# 004_FOC_RS_Interface.net
KiCad netlist of a schematic drawn in Altium Designer
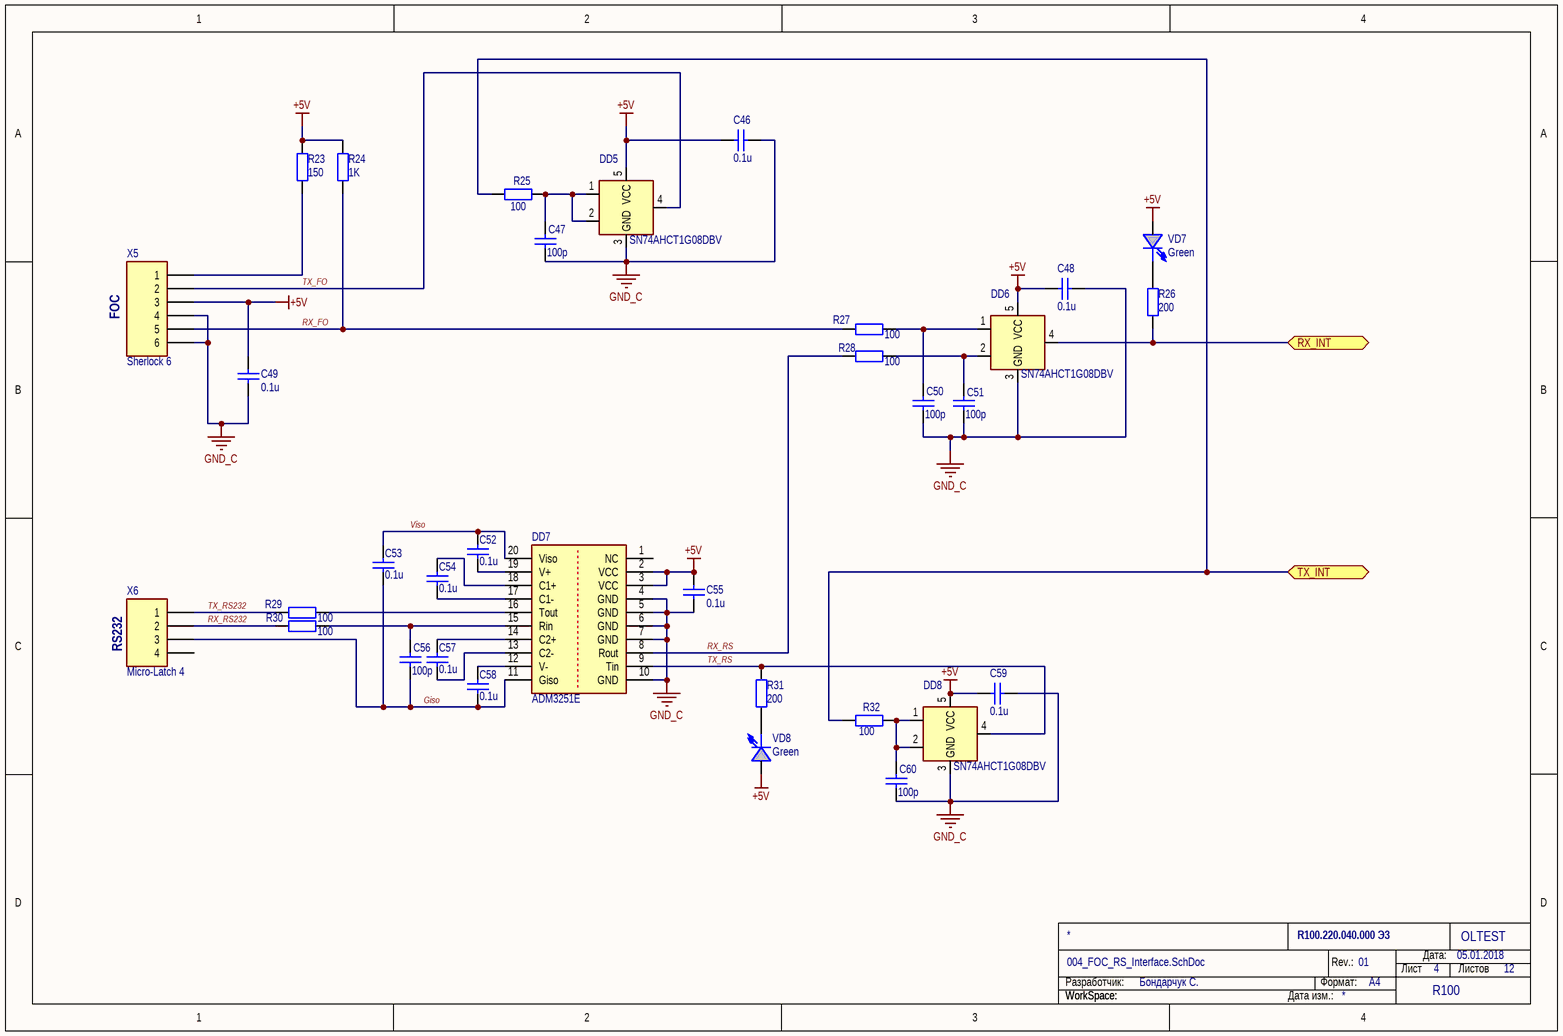
[diagram p0: 004_FOC_RS_Interface.SchDoc]

(export (version "E")
  (design (tool "Eeschema 10.0.6"))
  (components
    (comp (ref "C46")
      (value "0.1u")
      (footprint "mainLib:SMD_C_0603")
      (description "SMD C 0603 MURATA 50V 10% X7R")
      (fields (field (name "PARTNUMBER") "GRM188R71H104K") (field (name "MANUFACTURER") "MURATA"))
      (libsource (lib "mainRCLib") (part "C0603 0.1u 50V 10%"))
    )
    (comp (ref "C47")
      (value "100p")
      (footprint "mainLib:SMD_C_0603")
      (description "SMD C 0603 MURATA 100V 5% NP0")
      (fields (field (name "PARTNUMBER") "GRM1885C2A101JA01") (field (name "MANUFACTURER") "MURATA"))
      (libsource (lib "mainRCLib") (part "C0603 100p 100V 5%"))
    )
    (comp (ref "C48")
      (value "0.1u")
      (footprint "mainLib:SMD_C_0603")
      (description "SMD C 0603 MURATA 50V 10% X7R")
      (fields (field (name "PARTNUMBER") "GRM188R71H104K") (field (name "MANUFACTURER") "MURATA"))
      (libsource (lib "mainRCLib") (part "C0603 0.1u 50V 10%"))
    )
    (comp (ref "C49")
      (value "0.1u")
      (footprint "mainLib:SMD_C_0603")
      (description "SMD C 0603 MURATA 50V 10% X7R")
      (fields (field (name "PARTNUMBER") "GRM188R71H104K") (field (name "MANUFACTURER") "MURATA"))
      (libsource (lib "mainRCLib") (part "C0603 0.1u 50V 10%"))
    )
    (comp (ref "C50")
      (value "100p")
      (footprint "mainLib:SMD_C_0603")
      (description "SMD C 0603 MURATA 100V 5% NP0")
      (fields (field (name "PARTNUMBER") "GRM1885C2A101JA01") (field (name "MANUFACTURER") "MURATA"))
      (libsource (lib "mainRCLib") (part "C0603 100p 100V 5%"))
    )
    (comp (ref "C51")
      (value "100p")
      (footprint "mainLib:SMD_C_0603")
      (description "SMD C 0603 MURATA 100V 5% NP0")
      (fields (field (name "PARTNUMBER") "GRM1885C2A101JA01") (field (name "MANUFACTURER") "MURATA"))
      (libsource (lib "mainRCLib") (part "C0603 100p 100V 5%"))
    )
    (comp (ref "C52")
      (value "0.1u")
      (footprint "mainLib:SMD_C_0603")
      (description "SMD C 0603 MURATA 50V 10% X7R")
      (fields (field (name "PARTNUMBER") "GRM188R71H104K") (field (name "MANUFACTURER") "MURATA"))
      (libsource (lib "mainRCLib") (part "C0603 0.1u 50V 10%"))
    )
    (comp (ref "C53")
      (value "0.1u")
      (footprint "mainLib:SMD_C_0603")
      (description "SMD C 0603 MURATA 50V 10% X7R")
      (fields (field (name "PARTNUMBER") "GRM188R71H104K") (field (name "MANUFACTURER") "MURATA"))
      (libsource (lib "mainRCLib") (part "C0603 0.1u 50V 10%"))
    )
    (comp (ref "C54")
      (value "0.1u")
      (footprint "mainLib:SMD_C_0603")
      (description "SMD C 0603 MURATA 50V 10% X7R")
      (fields (field (name "PARTNUMBER") "GRM188R71H104K") (field (name "MANUFACTURER") "MURATA"))
      (libsource (lib "mainRCLib") (part "C0603 0.1u 50V 10%"))
    )
    (comp (ref "C55")
      (value "0.1u")
      (footprint "mainLib:SMD_C_0603")
      (description "SMD C 0603 MURATA 50V 10% X7R")
      (fields (field (name "PARTNUMBER") "GRM188R71H104K") (field (name "MANUFACTURER") "MURATA"))
      (libsource (lib "mainRCLib") (part "C0603 0.1u 50V 10%"))
    )
    (comp (ref "C56")
      (value "100p")
      (footprint "mainLib:SMD_C_0603")
      (description "SMD C 0603 MURATA 100V 5% NP0")
      (fields (field (name "PARTNUMBER") "GRM1885C2A101JA01") (field (name "MANUFACTURER") "MURATA"))
      (libsource (lib "mainRCLib") (part "C0603 100p 100V 5%"))
    )
    (comp (ref "C57")
      (value "0.1u")
      (footprint "mainLib:SMD_C_0603")
      (description "SMD C 0603 MURATA 50V 10% X7R")
      (fields (field (name "PARTNUMBER") "GRM188R71H104K") (field (name "MANUFACTURER") "MURATA"))
      (libsource (lib "mainRCLib") (part "C0603 0.1u 50V 10%"))
    )
    (comp (ref "C58")
      (value "0.1u")
      (footprint "mainLib:SMD_C_0603")
      (description "SMD C 0603 MURATA 50V 10% X7R")
      (fields (field (name "PARTNUMBER") "GRM188R71H104K") (field (name "MANUFACTURER") "MURATA"))
      (libsource (lib "mainRCLib") (part "C0603 0.1u 50V 10%"))
    )
    (comp (ref "C59")
      (value "0.1u")
      (footprint "mainLib:SMD_C_0603")
      (description "SMD C 0603 MURATA 50V 10% X7R")
      (fields (field (name "PARTNUMBER") "GRM188R71H104K") (field (name "MANUFACTURER") "MURATA"))
      (libsource (lib "mainRCLib") (part "C0603 0.1u 50V 10%"))
    )
    (comp (ref "C60")
      (value "100p")
      (footprint "mainLib:SMD_C_0603")
      (description "SMD C 0603 MURATA 100V 5% NP0")
      (fields (field (name "PARTNUMBER") "GRM1885C2A101JA01") (field (name "MANUFACTURER") "MURATA"))
      (libsource (lib "mainRCLib") (part "C0603 100p 100V 5%"))
    )
    (comp (ref "DD5")
      (value "SN74AHCT1G08DBV")
      (footprint "mainLib:SOT-23(DBV)")
      (description "2-in AND")
      (fields (field (name "MANUFACTURER") "Texas Instruments"))
      (libsource (lib "mainLib") (part "SN74AHCT1G08DBV"))
    )
    (comp (ref "DD6")
      (value "SN74AHCT1G08DBV")
      (footprint "mainLib:SOT-23(DBV)")
      (description "2-in AND")
      (fields (field (name "MANUFACTURER") "Texas Instruments"))
      (libsource (lib "mainLib") (part "SN74AHCT1G08DBV"))
    )
    (comp (ref "DD7")
      (value "ADM3251E")
      (footprint "mainLib:RW-20")
      (description "Isolated, Single-Channel, RS-232 Line Driver/Receiver")
      (fields (field (name "MANUFACTURER") "Analog Device") (field (name "PARTNUMBER") "ADM3251EARWZ"))
      (libsource (lib "mainLib") (part "ADM3251E"))
    )
    (comp (ref "DD8")
      (value "SN74AHCT1G08DBV")
      (footprint "mainLib:SOT-23(DBV)")
      (description "2-in AND")
      (fields (field (name "MANUFACTURER") "Texas Instruments"))
      (libsource (lib "mainLib") (part "SN74AHCT1G08DBV"))
    )
    (comp (ref "R23")
      (value "150")
      (footprint "mainLib:SMD_R_0805")
      (description "SMD 0805 VISHAY 0.125W 150V 1% 100ppm")
      (fields (field (name "PARTNUMBER") "CRCW0805150RFK") (field (name "MANUFACTURER") "VISHAY"))
      (libsource (lib "mainRCLib") (part "R0805 150 1%"))
    )
    (comp (ref "R24")
      (value "1K")
      (footprint "mainLib:SMD_R_0603")
      (description "SMD R 0603 VISHAY 0.1W 75V 1% 100ppm")
      (fields (field (name "PARTNUMBER") "CRCW06031K00FK") (field (name "MANUFACTURER") "VISHAY"))
      (libsource (lib "mainRCLib") (part "R0603 1K 1%"))
    )
    (comp (ref "R25")
      (value "100")
      (footprint "SMD_R_0603")
      (description "SMD R 0603 VISHAY 0.1W 75V 1% 100ppm")
      (fields (field (name "PARTNUMBER") "CRCW0603100RFK") (field (name "MANUFACTURER") "VISHAY"))
      (libsource (lib "mainRCLib") (part "R0603 100 1%"))
    )
    (comp (ref "R26")
      (value "200")
      (footprint "mainLib:SMD_R_0805")
      (description "SMD R 0805 VISHAY 0.125W 150V 1% 100ppm")
      (fields (field (name "PARTNUMBER") "CRCW0805200RFK") (field (name "MANUFACTURER") "VISHAY"))
      (libsource (lib "mainRCLib") (part "R0805 200 1%"))
    )
    (comp (ref "R27")
      (value "100")
      (footprint "SMD_R_0603")
      (description "SMD R 0603 VISHAY 0.1W 75V 1% 100ppm")
      (fields (field (name "PARTNUMBER") "CRCW0603100RFK") (field (name "MANUFACTURER") "VISHAY"))
      (libsource (lib "mainRCLib") (part "R0603 100 1%"))
    )
    (comp (ref "R28")
      (value "100")
      (footprint "SMD_R_0603")
      (description "SMD R 0603 VISHAY 0.1W 75V 1% 100ppm")
      (fields (field (name "PARTNUMBER") "CRCW0603100RFK") (field (name "MANUFACTURER") "VISHAY"))
      (libsource (lib "mainRCLib") (part "R0603 100 1%"))
    )
    (comp (ref "R29")
      (value "100")
      (footprint "SMD_R_0603")
      (description "SMD R 0603 VISHAY 0.1W 75V 1% 100ppm")
      (fields (field (name "PARTNUMBER") "CRCW0603100RFK") (field (name "MANUFACTURER") "VISHAY"))
      (libsource (lib "mainRCLib") (part "R0603 100 1%"))
    )
    (comp (ref "R30")
      (value "100")
      (footprint "SMD_R_0603")
      (description "SMD R 0603 VISHAY 0.1W 75V 1% 100ppm")
      (fields (field (name "PARTNUMBER") "CRCW0603100RFK") (field (name "MANUFACTURER") "VISHAY"))
      (libsource (lib "mainRCLib") (part "R0603 100 1%"))
    )
    (comp (ref "R31")
      (value "200")
      (footprint "mainLib:SMD_R_0805")
      (description "SMD R 0805 VISHAY 0.125W 150V 1% 100ppm")
      (fields (field (name "PARTNUMBER") "CRCW0805200RFK") (field (name "MANUFACTURER") "VISHAY"))
      (libsource (lib "mainRCLib") (part "R0805 200 1%"))
    )
    (comp (ref "R32")
      (value "100")
      (footprint "SMD_R_0603")
      (description "SMD R 0603 VISHAY 0.1W 75V 1% 100ppm")
      (fields (field (name "PARTNUMBER") "CRCW0603100RFK") (field (name "MANUFACTURER") "VISHAY"))
      (libsource (lib "mainRCLib") (part "R0603 100 1%"))
    )
    (comp (ref "VD7")
      (value "Green")
      (footprint "mainLib:SMD_LED_LL_Green")
      (description "LED Green SMD")
      (fields (field (name "PARTNUMBER") "LL-S172GC-2A") (field (name "MANUFACTURER") "Lucky Light"))
      (libsource (lib "mainLib") (part "LL-S172GC-2A"))
    )
    (comp (ref "VD8")
      (value "Green")
      (footprint "mainLib:SMD_LED_LL_Green")
      (description "LED Green SMD")
      (fields (field (name "PARTNUMBER") "LL-S172GC-2A") (field (name "MANUFACTURER") "Lucky Light"))
      (libsource (lib "mainLib") (part "LL-S172GC-2A"))
    )
    (comp (ref "X5")
      (value "Sherlock 6")
      (footprint "mainLib:35362-0650")
      (description "Sherlock 6 Side, 2A 125V 2mm")
      (fields (field (name "PARTNUMBER") "35362-0650") (field (name "MANUFACTURER") "MOLEX"))
      (libsource (lib "mainLib") (part "35363-0650"))
    )
    (comp (ref "X6")
      (value "Micro-Latch 4")
      (footprint "mainLib:53253-0470")
      (description "Micro-Latch 4  LS=2 2A 125V PCB")
      (fields (field (name "PARTNUMBER") "53253-0470") (field (name "MANUFACTURER") "MOLEX"))
      (libsource (lib "mainLib") (part "53253-0470"))
    )
  )
  (nets
    (net (code "1") (name "+5V") (class "Default")
      (node (ref "C46") (pin "1") (pinfunction "1_1") (pintype "passive"))
      (node (ref "C48") (pin "1") (pinfunction "1_1") (pintype "passive"))
      (node (ref "C49") (pin "2") (pinfunction "2_2") (pintype "passive"))
      (node (ref "C55") (pin "2") (pinfunction "2_2") (pintype "passive"))
      (node (ref "C59") (pin "1") (pinfunction "1_1") (pintype "passive"))
      (node (ref "DD5") (pin "5") (pinfunction "VCC_5") (pintype "passive"))
      (node (ref "DD6") (pin "5") (pinfunction "VCC_5") (pintype "passive"))
      (node (ref "DD7") (pin "2") (pinfunction "VCC_2") (pintype "power_in"))
      (node (ref "DD7") (pin "3") (pinfunction "VCC_3") (pintype "power_in"))
      (node (ref "DD8") (pin "5") (pinfunction "VCC_5") (pintype "passive"))
      (node (ref "R23") (pin "2") (pinfunction "2_2") (pintype "passive"))
      (node (ref "R24") (pin "2") (pinfunction "2_2") (pintype "passive"))
      (node (ref "VD7") (pin "1") (pinfunction "ANODE_1") (pintype "passive"))
      (node (ref "VD8") (pin "1") (pinfunction "ANODE_1") (pintype "passive"))
      (node (ref "X5") (pin "3") (pinfunction "3_3") (pintype "passive"))
    )
    (net (code "2") (name "/Giso") (class "Default")
      (node (ref "C53") (pin "1") (pinfunction "1_1") (pintype "passive"))
      (node (ref "C56") (pin "1") (pinfunction "1_1") (pintype "passive"))
      (node (ref "C58") (pin "1") (pinfunction "1_1") (pintype "passive"))
      (node (ref "DD7") (pin "11") (pinfunction "Giso_11") (pintype "passive"))
      (node (ref "X6") (pin "3") (pinfunction "3_3") (pintype "passive"))
    )
    (net (code "3") (name "/RX_FO") (class "Default")
      (node (ref "R24") (pin "1") (pinfunction "1_1") (pintype "passive"))
      (node (ref "R27") (pin "1") (pinfunction "1_1") (pintype "passive"))
      (node (ref "X5") (pin "5") (pinfunction "5_5") (pintype "passive"))
    )
    (net (code "4") (name "/RX_INT") (class "Default")
      (node (ref "DD6") (pin "4") (pintype "passive"))
      (node (ref "R26") (pin "1") (pinfunction "1_1") (pintype "passive"))
    )
    (net (code "5") (name "/RX_RS") (class "Default")
      (node (ref "DD7") (pin "8") (pinfunction "Rout_8") (pintype "passive"))
      (node (ref "R28") (pin "1") (pinfunction "1_1") (pintype "passive"))
    )
    (net (code "6") (name "/RX_RS232") (class "Default")
      (node (ref "R30") (pin "1") (pinfunction "1_1") (pintype "passive"))
      (node (ref "X6") (pin "2") (pinfunction "2_2") (pintype "passive"))
    )
    (net (code "7") (name "/TX_FO") (class "Default")
      (node (ref "DD5") (pin "4") (pintype "passive"))
      (node (ref "X5") (pin "2") (pinfunction "2_2") (pintype "passive"))
    )
    (net (code "8") (name "/TX_INT") (class "Default")
      (node (ref "R25") (pin "1") (pinfunction "1_1") (pintype "passive"))
      (node (ref "R32") (pin "1") (pinfunction "1_1") (pintype "passive"))
    )
    (net (code "9") (name "/TX_RS") (class "Default")
      (node (ref "DD7") (pin "9") (pinfunction "Tin_9") (pintype "passive"))
      (node (ref "DD8") (pin "4") (pintype "passive"))
      (node (ref "R31") (pin "2") (pinfunction "2_2") (pintype "passive"))
    )
    (net (code "10") (name "/TX_RS232") (class "Default")
      (node (ref "R29") (pin "1") (pinfunction "1_1") (pintype "passive"))
      (node (ref "X6") (pin "1") (pinfunction "1_1") (pintype "passive"))
    )
    (net (code "11") (name "/Viso") (class "Default")
      (node (ref "C52") (pin "2") (pinfunction "2_2") (pintype "passive"))
      (node (ref "C53") (pin "2") (pinfunction "2_2") (pintype "passive"))
      (node (ref "DD7") (pin "20") (pinfunction "Viso_20") (pintype "passive"))
    )
    (net (code "12") (name "GND_C") (class "Default")
      (node (ref "C46") (pin "2") (pinfunction "2_2") (pintype "passive"))
      (node (ref "C47") (pin "1") (pinfunction "1_1") (pintype "passive"))
      (node (ref "C48") (pin "2") (pinfunction "2_2") (pintype "passive"))
      (node (ref "C49") (pin "1") (pinfunction "1_1") (pintype "passive"))
      (node (ref "C50") (pin "1") (pinfunction "1_1") (pintype "passive"))
      (node (ref "C51") (pin "2") (pinfunction "2_2") (pintype "passive"))
      (node (ref "C55") (pin "1") (pinfunction "1_1") (pintype "passive"))
      (node (ref "C59") (pin "2") (pinfunction "2_2") (pintype "passive"))
      (node (ref "C60") (pin "1") (pinfunction "1_1") (pintype "passive"))
      (node (ref "DD5") (pin "3") (pinfunction "GND_3") (pintype "passive"))
      (node (ref "DD6") (pin "3") (pinfunction "GND_3") (pintype "passive"))
      (node (ref "DD7") (pin "10") (pinfunction "GND_10") (pintype "power_in"))
      (node (ref "DD7") (pin "4") (pinfunction "GND_4") (pintype "power_in"))
      (node (ref "DD7") (pin "5") (pinfunction "GND_5") (pintype "power_in"))
      (node (ref "DD7") (pin "6") (pinfunction "GND_6") (pintype "power_in"))
      (node (ref "DD7") (pin "7") (pinfunction "GND_7") (pintype "power_in"))
      (node (ref "DD8") (pin "3") (pinfunction "GND_3") (pintype "passive"))
      (node (ref "X5") (pin "4") (pinfunction "4_4") (pintype "passive"))
      (node (ref "X5") (pin "6") (pinfunction "6_6") (pintype "passive"))
    )
    (net (code "13") (name "Net-(C47-Pad2)") (class "Default")
      (node (ref "C47") (pin "2") (pinfunction "2_2") (pintype "passive"))
      (node (ref "DD5") (pin "1") (pintype "passive"))
      (node (ref "DD5") (pin "2") (pintype "passive"))
      (node (ref "R25") (pin "2") (pinfunction "2_2") (pintype "passive"))
    )
    (net (code "14") (name "Net-(C50-Pad2)") (class "Default")
      (node (ref "C50") (pin "2") (pinfunction "2_2") (pintype "passive"))
      (node (ref "DD6") (pin "1") (pintype "passive"))
      (node (ref "R27") (pin "2") (pinfunction "2_2") (pintype "passive"))
    )
    (net (code "15") (name "Net-(C51-Pad1)") (class "Default")
      (node (ref "C51") (pin "1") (pinfunction "1_1") (pintype "passive"))
      (node (ref "DD6") (pin "2") (pintype "passive"))
      (node (ref "R28") (pin "2") (pinfunction "2_2") (pintype "passive"))
    )
    (net (code "16") (name "Net-(C60-Pad2)") (class "Default")
      (node (ref "C60") (pin "2") (pinfunction "2_2") (pintype "passive"))
      (node (ref "DD8") (pin "1") (pintype "passive"))
      (node (ref "DD8") (pin "2") (pintype "passive"))
      (node (ref "R32") (pin "2") (pinfunction "2_2") (pintype "passive"))
    )
    (net (code "17") (name "Net-(DD7-C1+)") (class "Default")
      (node (ref "C54") (pin "2") (pinfunction "2_2") (pintype "passive"))
      (node (ref "DD7") (pin "18") (pinfunction "C1+_18") (pintype "passive"))
    )
    (net (code "18") (name "Net-(DD7-C1-)") (class "Default")
      (node (ref "C54") (pin "1") (pinfunction "1_1") (pintype "passive"))
      (node (ref "DD7") (pin "17") (pinfunction "C1-_17") (pintype "passive"))
    )
    (net (code "19") (name "Net-(DD7-C2+)") (class "Default")
      (node (ref "C57") (pin "2") (pinfunction "2_2") (pintype "passive"))
      (node (ref "DD7") (pin "14") (pinfunction "C2+_14") (pintype "passive"))
    )
    (net (code "20") (name "Net-(DD7-C2-)") (class "Default")
      (node (ref "C57") (pin "1") (pinfunction "1_1") (pintype "passive"))
      (node (ref "DD7") (pin "13") (pinfunction "C2-_13") (pintype "passive"))
    )
    (net (code "21") (name "Net-(DD7-Rin)") (class "Default")
      (node (ref "C56") (pin "2") (pinfunction "2_2") (pintype "passive"))
      (node (ref "DD7") (pin "15") (pinfunction "Rin_15") (pintype "passive"))
      (node (ref "R30") (pin "2") (pinfunction "2_2") (pintype "passive"))
    )
    (net (code "22") (name "Net-(DD7-Tout)") (class "Default")
      (node (ref "DD7") (pin "16") (pinfunction "Tout_16") (pintype "passive"))
      (node (ref "R29") (pin "2") (pinfunction "2_2") (pintype "passive"))
    )
    (net (code "23") (name "Net-(DD7-V+)") (class "Default")
      (node (ref "C52") (pin "1") (pinfunction "1_1") (pintype "passive"))
      (node (ref "DD7") (pin "19") (pinfunction "V+_19") (pintype "passive"))
    )
    (net (code "24") (name "Net-(DD7-V-)") (class "Default")
      (node (ref "C58") (pin "2") (pinfunction "2_2") (pintype "passive"))
      (node (ref "DD7") (pin "12") (pinfunction "V-_12") (pintype "passive"))
    )
    (net (code "25") (name "Net-(R23-Pad1)") (class "Default")
      (node (ref "R23") (pin "1") (pinfunction "1_1") (pintype "passive"))
      (node (ref "X5") (pin "1") (pinfunction "1_1") (pintype "passive"))
    )
    (net (code "26") (name "Net-(VD7-CATHODE)") (class "Default")
      (node (ref "R26") (pin "2") (pinfunction "2_2") (pintype "passive"))
      (node (ref "VD7") (pin "2") (pinfunction "CATHODE_2") (pintype "passive"))
    )
    (net (code "27") (name "Net-(VD8-CATHODE)") (class "Default")
      (node (ref "R31") (pin "1") (pinfunction "1_1") (pintype "passive"))
      (node (ref "VD8") (pin "2") (pinfunction "CATHODE_2") (pintype "passive"))
    )
    (net (code "28") (name "unconnected-(DD7-NC-Pad1)") (class "Default")
      (node (ref "DD7") (pin "1") (pinfunction "NC_1") (pintype "passive"))
    )
    (net (code "29") (name "unconnected-(X6-Pad4)") (class "Default")
      (node (ref "X6") (pin "4") (pinfunction "4_4") (pintype "passive"))
    )
  )
)
